# 4_Sensoren.net
KiCad netlist of a schematic drawn in Altium Designer
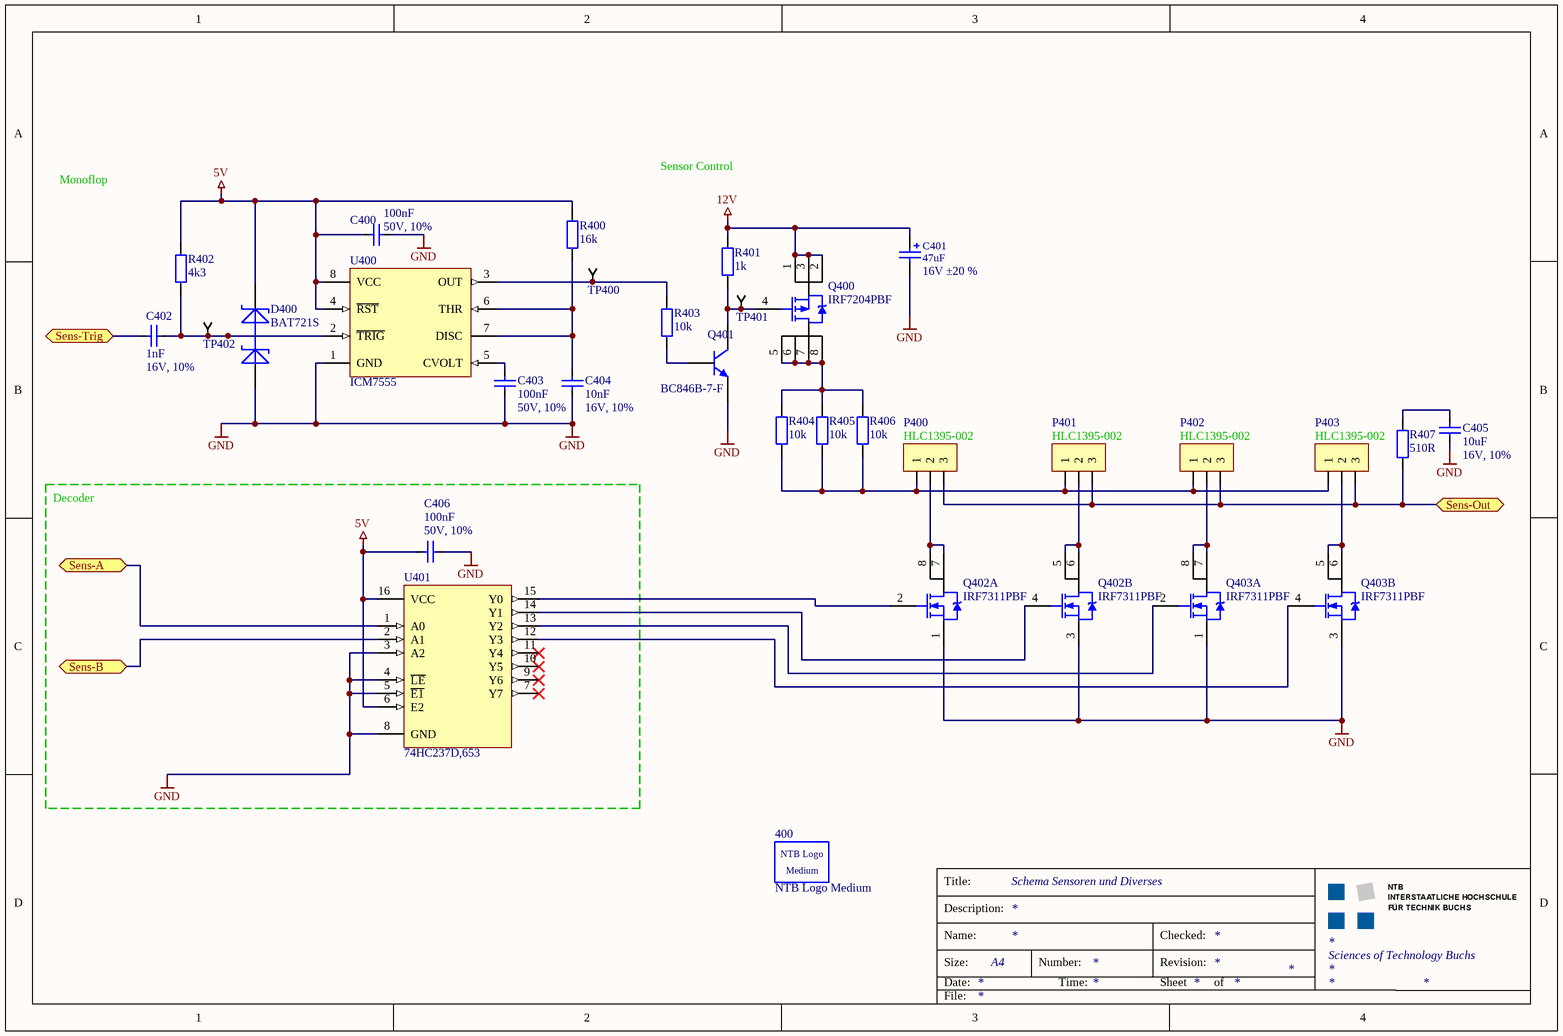
[diagram p0: 4_Sensoren.SchDoc]

(export (version "E")
  (design (tool "Eeschema 10.0.6"))
  (components
    (comp (ref "400")
      (value "NTB Logo Medium")
      (footprint "NTB Logo Medium")
      (libsource (lib "IR-Sensor") (part "NTB Logo Medium"))
    )
    (comp (ref "C400")
      (value "100nF")
      (footprint "CAP-0805[2012]")
      (description "100n 50V X7R MLCC 0805 (1608 Metric)")
      (fields (field (name "TOLERANCE") "10%") (field (name "VALADDON") "50V, 10%"))
      (libsource (lib "IR-Sensor") (part "MLCC 0805 100n 50V"))
    )
    (comp (ref "C401")
      (value "47uF")
      (footprint "CDE_CAP AVE CODE D_H")
      (description "ELKO, 47uF, 16V, CDE_AVE476M16D16T-F_AVE CODE D")
      (fields
        (field (name "MANUFACTURER") "Cornell Dubilier")
        (field (name "VALUEADDON") "16V ±20 %")
        (field (name "Comment") "AVE476M16D16T-F")
        (field (name "PUBLISHER") "Stefan Ursella, M.Eng")
      )
      (libsource (lib "IR-Sensor") (part "ELKO 47uF 16V"))
    )
    (comp (ref "C402")
      (value "1nF")
      (footprint "CAP-0805[2012]")
      (description "MLCC - SMD/SMT 0805 1000pF 16V C0G 10%")
      (fields
        (field (name "MANUFACTURER") "Vishay")
        (field (name "VALUEADDON") "16V, 10%")
        (field (name "PUBLISHER") "SCLM")
      )
      (libsource (lib "IR-Sensor") (part "MLCC 0805 1n 16V"))
    )
    (comp (ref "C403")
      (value "100nF")
      (footprint "CAP-0805[2012]")
      (description "100n 50V X7R MLCC 0805 (1608 Metric)")
      (fields (field (name "TOLERANCE") "10%") (field (name "VALADDON") "50V, 10%"))
      (libsource (lib "IR-Sensor") (part "MLCC 0805 100n 50V"))
    )
    (comp (ref "C404")
      (value "10nF")
      (footprint "CAP-0805[2012]")
      (description "10n 16V X7R MLCC 0805")
      (fields
        (field (name "MANUFACTURER") "AVX")
        (field (name "VALUEADDON") "16V, 10%")
        (field (name "PUBLISHER") "SCLM")
      )
      (libsource (lib "IR-Sensor") (part "MLCC 0805 10n 16V"))
    )
    (comp (ref "C405")
      (value "10uF")
      (footprint "CAP-1206[3216]")
      (description "10u 16V X7R MLCC 1206 (3016 Metric)")
      (fields (field (name "TOLERANCE") "10%") (field (name "VALADDON") "16V, 10%"))
      (libsource (lib "IR-Sensor") (part "MLCC 1206 10u 16V"))
    )
    (comp (ref "C406")
      (value "100nF")
      (footprint "CAP-0805[2012]")
      (description "100n 50V X7R MLCC 0805 (1608 Metric)")
      (fields (field (name "TOLERANCE") "10%") (field (name "VALADDON") "50V, 10%"))
      (libsource (lib "IR-Sensor") (part "MLCC 0805 100n 50V"))
    )
    (comp (ref "D400")
      (value "BAT721S")
      (footprint "SOT-23")
      (description "NXP  BAT721S  SCHOTTKY-DIODE, 2FACH")
      (fields (field (name "MANUFACTURER") "NXP") (field (name "PUBLISHER") "SCNP"))
      (libsource (lib "IR-Sensor") (part "BAT721S-SOT23"))
    )
    (comp (ref "P400")
      (value "3 Pin Header Buchse")
      (footprint "3PIN HEADER SOCKET 2.54MM")
      (description "3 Pin Header 2.54mm Buchse")
      (libsource (lib "IR-Sensor") (part "3 Pin Header Buchse"))
    )
    (comp (ref "P401")
      (value "3 Pin Header Buchse")
      (footprint "3PIN HEADER SOCKET 2.54MM")
      (description "3 Pin Header 2.54mm Buchse")
      (libsource (lib "IR-Sensor") (part "3 Pin Header Buchse"))
    )
    (comp (ref "P402")
      (value "3 Pin Header Buchse")
      (footprint "3PIN HEADER SOCKET 2.54MM")
      (description "3 Pin Header 2.54mm Buchse")
      (libsource (lib "IR-Sensor") (part "3 Pin Header Buchse"))
    )
    (comp (ref "P403")
      (value "3 Pin Header Buchse")
      (footprint "3PIN HEADER SOCKET 2.54MM")
      (description "3 Pin Header 2.54mm Buchse")
      (libsource (lib "IR-Sensor") (part "3 Pin Header Buchse"))
    )
    (comp (ref "Q400")
      (value "IRF7204PBF")
      (footprint "SOIC-8")
      (description "High Power P-Kanal Mosfet")
      (fields
        (field (name "MANUFACTURER") "International Rectifiers")
        (field (name "PUBLISHER") "Altium Limited")
      )
      (libsource (lib "IR-Sensor") (part "IRF7204"))
    )
    (comp (ref "Q401")
      (value "BC846B-7-F")
      (footprint "SOT-23")
      (description "NPN General-purpose Transistor")
      (fields (field (name "MANUFACTURER") "DIODES INC") (field (name "PUBLISHER") "Altium Limited"))
      (libsource (lib "IR-Sensor") (part "BC846B-SOT23"))
    )
    (comp (ref "Q402")
      (value "IRF7311PBF")
      (footprint "SOIC-8")
      (description "Dual N-Kanal Mosfet")
      (fields
        (field (name "MANUFACTURER") "International Rectifier")
        (field (name "PUBLISHER") "Altium Limited")
      )
      (libsource (lib "IR-Sensor") (part "IRF7311"))
    )
    (comp (ref "Q403")
      (value "IRF7311PBF")
      (footprint "SOIC-8")
      (description "Dual N-Kanal Mosfet")
      (fields
        (field (name "MANUFACTURER") "International Rectifier")
        (field (name "PUBLISHER") "Altium Limited")
      )
      (libsource (lib "IR-Sensor") (part "IRF7311"))
    )
    (comp (ref "R400")
      (value "16k")
      (footprint "RES-0805[2012]")
      (description "0805 (2013 Metric) 1/10 W 10K 1 Thick Film Chip Resistor")
      (fields (field (name "POWER") "1/10 W") (field (name "TOLERANCE") "1%"))
      (libsource (lib "IR-Sensor") (part "RES 0805"))
    )
    (comp (ref "R401")
      (value "1k")
      (footprint "RES-0805[2012]")
      (description "0805 (2013 Metric) 1/10 W 10K 1 Thick Film Chip Resistor")
      (fields (field (name "POWER") "1/10 W") (field (name "TOLERANCE") "1%"))
      (libsource (lib "IR-Sensor") (part "RES 0805"))
    )
    (comp (ref "R402")
      (value "4k3")
      (footprint "RES-0805[2012]")
      (description "0805 (2013 Metric) 1/10 W 10K 1 Thick Film Chip Resistor")
      (fields (field (name "POWER") "1/10 W") (field (name "TOLERANCE") "1%"))
      (libsource (lib "IR-Sensor") (part "RES 0805"))
    )
    (comp (ref "R403")
      (value "10k")
      (footprint "RES-0805[2012]")
      (description "0805 (2013 Metric) 1/10 W 10K 1 Thick Film Chip Resistor")
      (fields (field (name "POWER") "1/10 W") (field (name "TOLERANCE") "1%"))
      (libsource (lib "IR-Sensor") (part "RES 0805"))
    )
    (comp (ref "R404")
      (value "10k")
      (footprint "RES-0805[2012]")
      (description "0805 (2013 Metric) 1/10 W 10K 1 Thick Film Chip Resistor")
      (fields (field (name "POWER") "1/10 W") (field (name "TOLERANCE") "1%"))
      (libsource (lib "IR-Sensor") (part "RES 0805"))
    )
    (comp (ref "R405")
      (value "10k")
      (footprint "RES-0805[2012]")
      (description "0805 (2013 Metric) 1/10 W 10K 1 Thick Film Chip Resistor")
      (fields (field (name "POWER") "1/10 W") (field (name "TOLERANCE") "1%"))
      (libsource (lib "IR-Sensor") (part "RES 0805"))
    )
    (comp (ref "R406")
      (value "10k")
      (footprint "RES-0805[2012]")
      (description "0805 (2013 Metric) 1/10 W 10K 1 Thick Film Chip Resistor")
      (fields (field (name "POWER") "1/10 W") (field (name "TOLERANCE") "1%"))
      (libsource (lib "IR-Sensor") (part "RES 0805"))
    )
    (comp (ref "R407")
      (value "510R")
      (footprint "RES-0805[2012]")
      (description "0805 (2013 Metric) 1/10 W 10K 1 Thick Film Chip Resistor")
      (fields (field (name "POWER") "1/10 W") (field (name "TOLERANCE") "1%"))
      (libsource (lib "IR-Sensor") (part "RES 0805"))
    )
    (comp (ref "TP400")
      (value "Testpoint SMD 1206")
      (footprint "TP-SMD-1206")
      (description "Testpoint xSmall")
      (libsource (lib "IR-Sensor") (part "Testpoint SMD 1206"))
    )
    (comp (ref "TP401")
      (value "Testpoint SMD 1206")
      (footprint "TP-SMD-1206")
      (description "Testpoint xSmall")
      (libsource (lib "altium-import") (part "root_0_Testpoint SMD 1206_"))
    )
    (comp (ref "TP402")
      (value "Testpoint SMD 1206")
      (footprint "TP-SMD-1206")
      (description "Testpoint xSmall")
      (libsource (lib "IR-Sensor") (part "Testpoint SMD 1206"))
    )
    (comp (ref "U400")
      (value "ICM7555")
      (footprint "SOIC-8")
      (description "General purpose CMOS timer")
      (fields
        (field (name "MANUFACTURER") "National Semiconductor")
        (field (name "PUBLISHER") "Altium Hobart Technology Centre")
      )
      (libsource (lib "IR-Sensor") (part "ICM7555-SOIC8"))
    )
    (comp (ref "U401")
      (value "74HC237D,653")
      (footprint "SOIC-16")
      (description "3-to-8 line decoder, demultiplexer, NXP, SO16")
      (fields (field (name "MANUFACTURER") "NXP") (field (name "PUBLISHER") "SCLM"))
      (libsource (lib "IR-Sensor") (part "74HC237D-SOIC16"))
    )
  )
  (nets
    (net (code "1") (name "/Sens-A") (class "Default")
      (node (ref "U401") (pin "1") (pinfunction "A0_1") (pintype "input"))
    )
    (net (code "2") (name "/Sens-B") (class "Default")
      (node (ref "U401") (pin "2") (pinfunction "A1_2") (pintype "input"))
    )
    (net (code "3") (name "/Sens-Out") (class "Default")
      (node (ref "P400") (pin "3") (pinfunction "3_3") (pintype "passive"))
      (node (ref "P401") (pin "3") (pinfunction "3_3") (pintype "passive"))
      (node (ref "P402") (pin "3") (pinfunction "3_3") (pintype "passive"))
      (node (ref "P403") (pin "3") (pinfunction "3_3") (pintype "passive"))
      (node (ref "R407") (pin "1") (pinfunction "1_1") (pintype "passive"))
    )
    (net (code "4") (name "/Sens-Trig") (class "Default")
      (node (ref "C402") (pin "1") (pinfunction "Pos_1") (pintype "passive"))
    )
    (net (code "5") (name "5V") (class "Default")
      (node (ref "C400") (pin "1") (pinfunction "Pos_1") (pintype "passive"))
      (node (ref "C406") (pin "1") (pinfunction "Pos_1") (pintype "passive"))
      (node (ref "D400") (pin "2") (pinfunction "cathode2_2") (pintype "passive"))
      (node (ref "R400") (pin "2") (pinfunction "2_2") (pintype "passive"))
      (node (ref "R402") (pin "2") (pinfunction "2_2") (pintype "passive"))
      (node (ref "U400") (pin "4") (pinfunction "~{RST}_4") (pintype "input"))
      (node (ref "U400") (pin "8") (pinfunction "VCC_8") (pintype "power_in"))
      (node (ref "U401") (pin "16") (pinfunction "VCC_16") (pintype "power_in"))
      (node (ref "U401") (pin "6") (pinfunction "E2_6") (pintype "input"))
    )
    (net (code "6") (name "12V") (class "Default")
      (node (ref "C401") (pin "1") (pinfunction "Pos_1") (pintype "passive"))
      (node (ref "Q400") (pin "1") (pinfunction "S_1") (pintype "passive"))
      (node (ref "Q400") (pin "2") (pinfunction "S_2") (pintype "passive"))
      (node (ref "Q400") (pin "3") (pinfunction "S_3") (pintype "passive"))
      (node (ref "R401") (pin "2") (pinfunction "2_2") (pintype "passive"))
    )
    (net (code "7") (name "GND") (class "Default")
      (node (ref "C400") (pin "2") (pinfunction "Neg_2") (pintype "passive"))
      (node (ref "C401") (pin "2") (pinfunction "Neg_2") (pintype "passive"))
      (node (ref "C403") (pin "2") (pinfunction "Neg_2") (pintype "passive"))
      (node (ref "C404") (pin "2") (pinfunction "Neg_2") (pintype "passive"))
      (node (ref "C405") (pin "2") (pinfunction "Neg_2") (pintype "passive"))
      (node (ref "C406") (pin "2") (pinfunction "Neg_2") (pintype "passive"))
      (node (ref "D400") (pin "1") (pinfunction "Anode1_1") (pintype "passive"))
      (node (ref "Q401") (pin "2") (pinfunction "E_2") (pintype "passive"))
      (node (ref "Q402") (pin "1") (pinfunction "S_1") (pintype "passive"))
      (node (ref "Q402") (pin "3") (pinfunction "S_3") (pintype "passive"))
      (node (ref "Q403") (pin "1") (pinfunction "S_1") (pintype "passive"))
      (node (ref "Q403") (pin "3") (pinfunction "S_3") (pintype "passive"))
      (node (ref "U400") (pin "1") (pinfunction "GND_1") (pintype "power_in"))
      (node (ref "U401") (pin "3") (pinfunction "A2_3") (pintype "input"))
      (node (ref "U401") (pin "4") (pinfunction "LE_4") (pintype "input"))
      (node (ref "U401") (pin "5") (pinfunction "E1_5") (pintype "input"))
      (node (ref "U401") (pin "8") (pinfunction "GND_8") (pintype "power_in"))
    )
    (net (code "8") (name "Net-(C402-Neg)") (class "Default")
      (node (ref "C402") (pin "2") (pinfunction "Neg_2") (pintype "passive"))
      (node (ref "D400") (pin "3") (pinfunction "Cathode1,_anode2_3") (pintype "passive"))
      (node (ref "R402") (pin "1") (pinfunction "1_1") (pintype "passive"))
      (node (ref "TP402") (pin "1") (pinfunction "0_1") (pintype "passive"))
      (node (ref "U400") (pin "2") (pinfunction "TRIG_2") (pintype "input"))
    )
    (net (code "9") (name "Net-(C403-Pos)") (class "Default")
      (node (ref "C403") (pin "1") (pinfunction "Pos_1") (pintype "passive"))
      (node (ref "U400") (pin "5") (pinfunction "CVOLT_5") (pintype "input"))
    )
    (net (code "10") (name "Net-(C404-Pos)") (class "Default")
      (node (ref "C404") (pin "1") (pinfunction "Pos_1") (pintype "passive"))
      (node (ref "R400") (pin "1") (pinfunction "1_1") (pintype "passive"))
      (node (ref "U400") (pin "6") (pinfunction "THR_6") (pintype "input"))
      (node (ref "U400") (pin "7") (pinfunction "DISC_7") (pintype "open_collector"))
    )
    (net (code "11") (name "Net-(C405-Pos)") (class "Default")
      (node (ref "C405") (pin "1") (pinfunction "Pos_1") (pintype "passive"))
      (node (ref "R407") (pin "2") (pinfunction "2_2") (pintype "passive"))
    )
    (net (code "12") (name "Net-(P400-Pad1)") (class "Default")
      (node (ref "P400") (pin "1") (pinfunction "1_1") (pintype "passive"))
      (node (ref "P401") (pin "1") (pinfunction "1_1") (pintype "passive"))
      (node (ref "P402") (pin "1") (pinfunction "1_1") (pintype "passive"))
      (node (ref "P403") (pin "1") (pinfunction "1_1") (pintype "passive"))
      (node (ref "R404") (pin "1") (pinfunction "1_1") (pintype "passive"))
      (node (ref "R405") (pin "1") (pinfunction "1_1") (pintype "passive"))
      (node (ref "R406") (pin "1") (pinfunction "1_1") (pintype "passive"))
    )
    (net (code "13") (name "Net-(P400-Pad2)") (class "Default")
      (node (ref "P400") (pin "2") (pinfunction "2_2") (pintype "passive"))
      (node (ref "Q402") (pin "7") (pinfunction "D_7") (pintype "passive"))
      (node (ref "Q402") (pin "8") (pinfunction "D_8") (pintype "passive"))
    )
    (net (code "14") (name "Net-(P401-Pad2)") (class "Default")
      (node (ref "P401") (pin "2") (pinfunction "2_2") (pintype "passive"))
      (node (ref "Q402") (pin "5") (pinfunction "D_5") (pintype "passive"))
      (node (ref "Q402") (pin "6") (pinfunction "D_6") (pintype "passive"))
    )
    (net (code "15") (name "Net-(P402-Pad2)") (class "Default")
      (node (ref "P402") (pin "2") (pinfunction "2_2") (pintype "passive"))
      (node (ref "Q403") (pin "7") (pinfunction "D_7") (pintype "passive"))
      (node (ref "Q403") (pin "8") (pinfunction "D_8") (pintype "passive"))
    )
    (net (code "16") (name "Net-(P403-Pad2)") (class "Default")
      (node (ref "P403") (pin "2") (pinfunction "2_2") (pintype "passive"))
      (node (ref "Q403") (pin "5") (pinfunction "D_5") (pintype "passive"))
      (node (ref "Q403") (pin "6") (pinfunction "D_6") (pintype "passive"))
    )
    (net (code "17") (name "Net-(Q400-D-Pad5)") (class "Default")
      (node (ref "Q400") (pin "5") (pinfunction "D_5") (pintype "passive"))
      (node (ref "Q400") (pin "6") (pinfunction "D_6") (pintype "passive"))
      (node (ref "Q400") (pin "7") (pinfunction "D_7") (pintype "passive"))
      (node (ref "Q400") (pin "8") (pinfunction "D_8") (pintype "passive"))
      (node (ref "R404") (pin "2") (pinfunction "2_2") (pintype "passive"))
      (node (ref "R405") (pin "2") (pinfunction "2_2") (pintype "passive"))
      (node (ref "R406") (pin "2") (pinfunction "2_2") (pintype "passive"))
    )
    (net (code "18") (name "Net-(Q400-G)") (class "Default")
      (node (ref "Q400") (pin "4") (pinfunction "G_4") (pintype "passive"))
      (node (ref "Q401") (pin "3") (pinfunction "C_3") (pintype "passive"))
      (node (ref "R401") (pin "1") (pinfunction "1_1") (pintype "passive"))
      (node (ref "TP401") (pin "1") (pinfunction "0_1") (pintype "passive"))
    )
    (net (code "19") (name "Net-(Q401-B)") (class "Default")
      (node (ref "Q401") (pin "1") (pinfunction "B_1") (pintype "passive"))
      (node (ref "R403") (pin "2") (pinfunction "2_2") (pintype "passive"))
    )
    (net (code "20") (name "Net-(Q402A-G)") (class "Default")
      (node (ref "Q402") (pin "2") (pinfunction "G_2") (pintype "passive"))
      (node (ref "U401") (pin "15") (pinfunction "Y0_15") (pintype "output"))
    )
    (net (code "21") (name "Net-(Q402B-G)") (class "Default")
      (node (ref "Q402") (pin "4") (pinfunction "G_4") (pintype "passive"))
      (node (ref "U401") (pin "14") (pinfunction "Y1_14") (pintype "output"))
    )
    (net (code "22") (name "Net-(Q403A-G)") (class "Default")
      (node (ref "Q403") (pin "2") (pinfunction "G_2") (pintype "passive"))
      (node (ref "U401") (pin "13") (pinfunction "Y2_13") (pintype "output"))
    )
    (net (code "23") (name "Net-(Q403B-G)") (class "Default")
      (node (ref "Q403") (pin "4") (pinfunction "G_4") (pintype "passive"))
      (node (ref "U401") (pin "12") (pinfunction "Y3_12") (pintype "output"))
    )
    (net (code "24") (name "Net-(TP400-0)") (class "Default")
      (node (ref "R403") (pin "1") (pinfunction "1_1") (pintype "passive"))
      (node (ref "TP400") (pin "1") (pinfunction "0_1") (pintype "passive"))
      (node (ref "U400") (pin "3") (pinfunction "OUT_3") (pintype "output"))
    )
    (net (code "25") (name "unconnected-(U401-Y4-Pad11)") (class "Default")
      (node (ref "U401") (pin "11") (pinfunction "Y4_11") (pintype "output+no_connect"))
    )
    (net (code "26") (name "unconnected-(U401-Y5-Pad10)") (class "Default")
      (node (ref "U401") (pin "10") (pinfunction "Y5_10") (pintype "output+no_connect"))
    )
    (net (code "27") (name "unconnected-(U401-Y6-Pad9)") (class "Default")
      (node (ref "U401") (pin "9") (pinfunction "Y6_9") (pintype "output+no_connect"))
    )
    (net (code "28") (name "unconnected-(U401-Y7-Pad7)") (class "Default")
      (node (ref "U401") (pin "7") (pinfunction "Y7_7") (pintype "output+no_connect"))
    )
  )
)
